# SCH_Orto-Idroponico_2021-09-24.net
KiCad netlist of a schematic drawn in EasyEDA
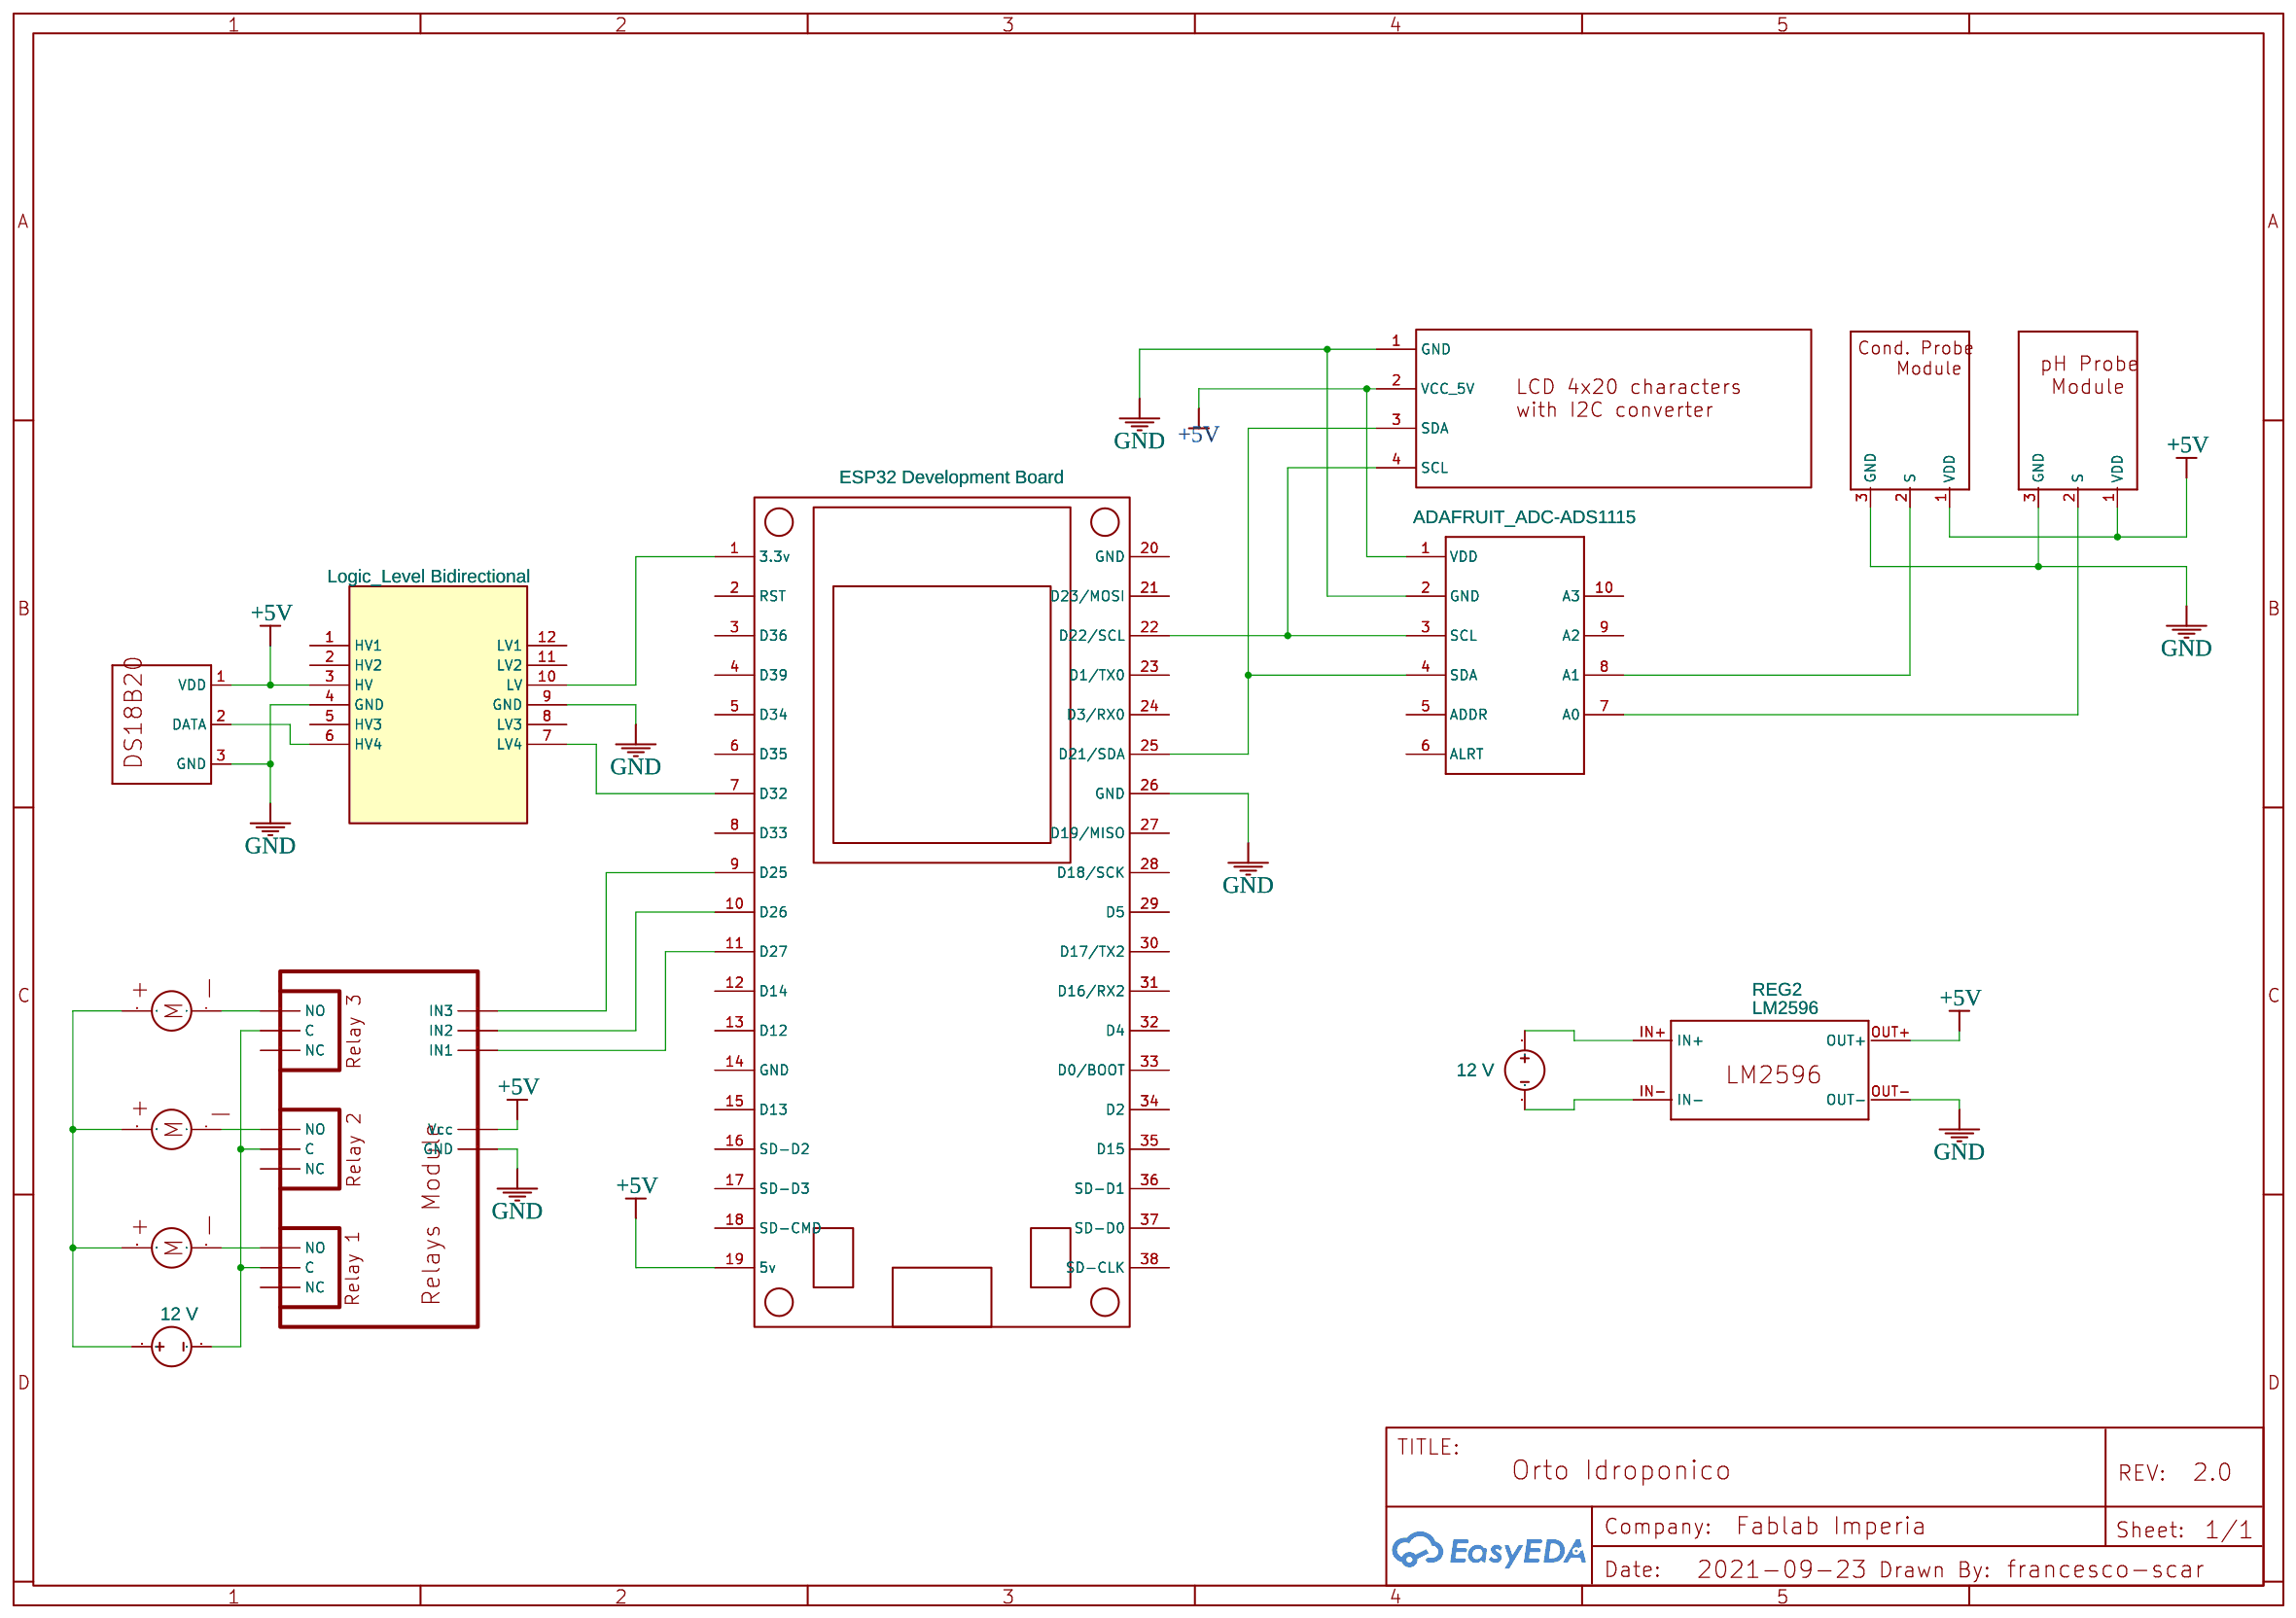
[diagram p0: schematic sheet]

(export (version "E")
  (design (tool "Eeschema 10.0.6"))
  (components
    (comp (ref "2") (value "ADAFRUIT_ADC-ADS1115") (libsource (lib "") (part "ADAFRUIT_ADC-ADS1115")))
    (comp (ref "P1")
      (value "Logic_Level Bidirectional")
      (libsource (lib "") (part "Logic_Level Bidirectional"))
    )
    (comp (ref "REG2") (value "LM2596") (libsource (lib "") (part "LM2596")))
    (comp (ref "T1") (value "DS18B20") (libsource (lib "") (part "DS18B20")))
    (comp (ref "T2") (value "pH probe module") (libsource (lib "") (part "pH probe module")))
    (comp (ref "T3")
      (value "conductivity probe module")
      (libsource (lib "") (part "conductivity probe module"))
    )
    (comp (ref "U1") (value "ESP32 Development Board") (libsource (lib "") (part "ESP32 Development Board")))
    (comp (ref "U2")
      (value "3_RELAYS_MODULE")
      (fields (field (name "BOM_Manufacturer Part") "3 Relays Module"))
      (libsource (lib "") (part "3_RELAYS_MODULE"))
    )
    (comp (ref "U3")
      (value "Nettigo LCD 4x20 I2C")
      (fields (field (name "BOM_Manufacturer Part") "2004A"))
      (libsource (lib "") (part "Nettigo LCD 4x20 I2C"))
    )
    (comp (ref "U4") (value "DC Motor") (libsource (lib "") (part "DC Motor")))
    (comp (ref "U5") (value "DC Motor") (libsource (lib "") (part "DC Motor_1")))
    (comp (ref "U6") (value "DC Motor") (libsource (lib "") (part "DC Motor")))
    (comp (ref "V1") (value "12 V") (libsource (lib "") (part "DC Power Source")))
    (comp (ref "V2") (value "12 V") (libsource (lib "") (part "DC Power Source_1")))
  )
  (nets
    (net (code "1") (name "+5V") (class "Default")
      (node (ref "2") (pin "1") (pinfunction "VDD_1") (pintype "bidirectional"))
      (node (ref "P1") (pin "3") (pinfunction "HV_3") (pintype "unspecified"))
      (node (ref "REG2") (pin "OUT+") (pinfunction "OUT+_OUT+") (pintype "bidirectional"))
      (node (ref "T1") (pin "1") (pinfunction "VDD_1") (pintype "passive"))
      (node (ref "T2") (pin "1") (pinfunction "VDD_1") (pintype "passive"))
      (node (ref "T3") (pin "1") (pinfunction "VDD_1") (pintype "passive"))
      (node (ref "U1") (pin "19") (pinfunction "5v_19") (pintype "passive"))
      (node (ref "U2") (pin "5") (pinfunction "Vcc_5") (pintype "unspecified"))
      (node (ref "U3") (pin "2") (pinfunction "VCC_5V_2") (pintype "unspecified"))
    )
    (net (code "2") (name "GND") (class "Default")
      (node (ref "2") (pin "2") (pinfunction "GND_2") (pintype "bidirectional"))
      (node (ref "P1") (pin "4") (pinfunction "GND_4") (pintype "unspecified"))
      (node (ref "P1") (pin "9") (pinfunction "GND_9") (pintype "unspecified"))
      (node (ref "REG2") (pin "OUT-") (pinfunction "OUT-_OUT-") (pintype "bidirectional"))
      (node (ref "T1") (pin "3") (pinfunction "GND_3") (pintype "passive"))
      (node (ref "T2") (pin "3") (pinfunction "GND_3") (pintype "passive"))
      (node (ref "T3") (pin "3") (pinfunction "GND_3") (pintype "passive"))
      (node (ref "U1") (pin "26") (pinfunction "GND_26") (pintype "passive"))
      (node (ref "U2") (pin "1") (pinfunction "GND_1") (pintype "unspecified"))
      (node (ref "U3") (pin "1") (pinfunction "GND_1") (pintype "unspecified"))
    )
    (net (code "3") (name "Net-(2-A0)") (class "Default")
      (node (ref "2") (pin "7") (pinfunction "A0_7") (pintype "bidirectional"))
      (node (ref "T2") (pin "2") (pinfunction "S_2") (pintype "unspecified"))
    )
    (net (code "4") (name "Net-(2-A1)") (class "Default")
      (node (ref "2") (pin "8") (pinfunction "A1_8") (pintype "bidirectional"))
      (node (ref "T3") (pin "2") (pinfunction "S_2") (pintype "unspecified"))
    )
    (net (code "5") (name "Net-(2-SCL)") (class "Default")
      (node (ref "2") (pin "3") (pinfunction "SCL_3") (pintype "bidirectional"))
      (node (ref "U1") (pin "22") (pinfunction "D22/SCL_22") (pintype "bidirectional"))
      (node (ref "U3") (pin "4") (pinfunction "SCL_4") (pintype "unspecified"))
    )
    (net (code "6") (name "Net-(2-SDA)") (class "Default")
      (node (ref "2") (pin "4") (pinfunction "SDA_4") (pintype "bidirectional"))
      (node (ref "U1") (pin "25") (pinfunction "D21/SDA_25") (pintype "bidirectional"))
      (node (ref "U3") (pin "3") (pinfunction "SDA_3") (pintype "unspecified"))
    )
    (net (code "7") (name "Net-(P1-HV4)") (class "Default")
      (node (ref "P1") (pin "6") (pinfunction "HV4_6") (pintype "unspecified"))
      (node (ref "T1") (pin "2") (pinfunction "DATA_2") (pintype "unspecified"))
    )
    (net (code "8") (name "Net-(P1-LV)") (class "Default")
      (node (ref "P1") (pin "10") (pinfunction "LV_10") (pintype "unspecified"))
      (node (ref "U1") (pin "1") (pinfunction "3.3v_1") (pintype "passive"))
    )
    (net (code "9") (name "Net-(P1-LV4)") (class "Default")
      (node (ref "P1") (pin "7") (pinfunction "LV4_7") (pintype "unspecified"))
      (node (ref "U1") (pin "7") (pinfunction "D32_7") (pintype "bidirectional"))
    )
    (net (code "10") (name "Net-(REG2-PadIN+)") (class "Default")
      (node (ref "REG2") (pin "IN+") (pinfunction "IN+_IN+") (pintype "bidirectional"))
      (node (ref "V1") (pin "1") (pinfunction "1_1") (pintype "unspecified"))
    )
    (net (code "11") (name "Net-(REG2-PadIN-)") (class "Default")
      (node (ref "REG2") (pin "IN-") (pinfunction "IN-_IN-") (pintype "bidirectional"))
      (node (ref "V1") (pin "2") (pinfunction "2_2") (pintype "unspecified"))
    )
    (net (code "12") (name "Net-(U1-D25)") (class "Default")
      (node (ref "U1") (pin "9") (pinfunction "D25_9") (pintype "bidirectional"))
      (node (ref "U2") (pin "4") (pinfunction "IN3_4") (pintype "unspecified"))
    )
    (net (code "13") (name "Net-(U1-D26)") (class "Default")
      (node (ref "U1") (pin "10") (pinfunction "D26_10") (pintype "bidirectional"))
      (node (ref "U2") (pin "3") (pinfunction "IN2_3") (pintype "unspecified"))
    )
    (net (code "14") (name "Net-(U1-D27)") (class "Default")
      (node (ref "U1") (pin "11") (pinfunction "D27_11") (pintype "bidirectional"))
      (node (ref "U2") (pin "2") (pinfunction "IN1_2") (pintype "unspecified"))
    )
    (net (code "15") (name "Net-(U2-C-Pad10)") (class "Default")
      (node (ref "U2") (pin "10") (pinfunction "C_10") (pintype "unspecified"))
      (node (ref "U2") (pin "13") (pinfunction "C_13") (pintype "unspecified"))
      (node (ref "U2") (pin "16") (pinfunction "C_16") (pintype "unspecified"))
      (node (ref "V2") (pin "2") (pinfunction "2_2") (pintype "unspecified"))
    )
    (net (code "16") (name "Net-(U2-NO-Pad11)") (class "Default")
      (node (ref "U2") (pin "11") (pinfunction "NO_11") (pintype "unspecified"))
      (node (ref "U6") (pin "1") (pinfunction "1_1") (pintype "unspecified"))
    )
    (net (code "17") (name "Net-(U2-NO-Pad14)") (class "Default")
      (node (ref "U2") (pin "14") (pinfunction "NO_14") (pintype "unspecified"))
      (node (ref "U5") (pin "1") (pinfunction "1_1") (pintype "unspecified"))
    )
    (net (code "18") (name "Net-(U2-NO-Pad17)") (class "Default")
      (node (ref "U2") (pin "17") (pinfunction "NO_17") (pintype "unspecified"))
      (node (ref "U4") (pin "1") (pinfunction "1_1") (pintype "unspecified"))
    )
    (net (code "19") (name "Net-(U4-Pad2)") (class "Default")
      (node (ref "U4") (pin "2") (pinfunction "2_2") (pintype "unspecified"))
      (node (ref "U5") (pin "2") (pinfunction "2_2") (pintype "unspecified"))
      (node (ref "U6") (pin "2") (pinfunction "2_2") (pintype "unspecified"))
      (node (ref "V2") (pin "1") (pinfunction "1_1") (pintype "unspecified"))
    )
    (net (code "20") (name "unconnected-(2-A2-Pad9)") (class "Default")
      (node (ref "2") (pin "9") (pinfunction "A2_9") (pintype "bidirectional"))
    )
    (net (code "21") (name "unconnected-(2-A3-Pad10)") (class "Default")
      (node (ref "2") (pin "10") (pinfunction "A3_10") (pintype "bidirectional"))
    )
    (net (code "22") (name "unconnected-(2-ADDR-Pad5)") (class "Default")
      (node (ref "2") (pin "5") (pinfunction "ADDR_5") (pintype "bidirectional"))
    )
    (net (code "23") (name "unconnected-(2-ALRT-Pad6)") (class "Default")
      (node (ref "2") (pin "6") (pinfunction "ALRT_6") (pintype "bidirectional"))
    )
    (net (code "24") (name "unconnected-(P1-HV1-Pad1)") (class "Default")
      (node (ref "P1") (pin "1") (pinfunction "HV1_1") (pintype "unspecified"))
    )
    (net (code "25") (name "unconnected-(P1-HV2-Pad2)") (class "Default")
      (node (ref "P1") (pin "2") (pinfunction "HV2_2") (pintype "unspecified"))
    )
    (net (code "26") (name "unconnected-(P1-HV3-Pad5)") (class "Default")
      (node (ref "P1") (pin "5") (pinfunction "HV3_5") (pintype "unspecified"))
    )
    (net (code "27") (name "unconnected-(P1-LV1-Pad12)") (class "Default")
      (node (ref "P1") (pin "12") (pinfunction "LV1_12") (pintype "unspecified"))
    )
    (net (code "28") (name "unconnected-(P1-LV2-Pad11)") (class "Default")
      (node (ref "P1") (pin "11") (pinfunction "LV2_11") (pintype "unspecified"))
    )
    (net (code "29") (name "unconnected-(P1-LV3-Pad8)") (class "Default")
      (node (ref "P1") (pin "8") (pinfunction "LV3_8") (pintype "unspecified"))
    )
    (net (code "30") (name "unconnected-(U1-D0{slash}BOOT-Pad33)") (class "Default")
      (node (ref "U1") (pin "33") (pinfunction "D0/BOOT_33") (pintype "bidirectional"))
    )
    (net (code "31") (name "unconnected-(U1-D1{slash}TX0-Pad23)") (class "Default")
      (node (ref "U1") (pin "23") (pinfunction "D1/TX0_23") (pintype "bidirectional"))
    )
    (net (code "32") (name "unconnected-(U1-D2-Pad34)") (class "Default")
      (node (ref "U1") (pin "34") (pinfunction "D2_34") (pintype "bidirectional"))
    )
    (net (code "33") (name "unconnected-(U1-D3{slash}RX0-Pad24)") (class "Default")
      (node (ref "U1") (pin "24") (pinfunction "D3/RX0_24") (pintype "bidirectional"))
    )
    (net (code "34") (name "unconnected-(U1-D4-Pad32)") (class "Default")
      (node (ref "U1") (pin "32") (pinfunction "D4_32") (pintype "bidirectional"))
    )
    (net (code "35") (name "unconnected-(U1-D5-Pad29)") (class "Default")
      (node (ref "U1") (pin "29") (pinfunction "D5_29") (pintype "bidirectional"))
    )
    (net (code "36") (name "unconnected-(U1-D12-Pad13)") (class "Default")
      (node (ref "U1") (pin "13") (pinfunction "D12_13") (pintype "bidirectional"))
    )
    (net (code "37") (name "unconnected-(U1-D13-Pad15)") (class "Default")
      (node (ref "U1") (pin "15") (pinfunction "D13_15") (pintype "bidirectional"))
    )
    (net (code "38") (name "unconnected-(U1-D14-Pad12)") (class "Default")
      (node (ref "U1") (pin "12") (pinfunction "D14_12") (pintype "bidirectional"))
    )
    (net (code "39") (name "unconnected-(U1-D15-Pad35)") (class "Default")
      (node (ref "U1") (pin "35") (pinfunction "D15_35") (pintype "bidirectional"))
    )
    (net (code "40") (name "unconnected-(U1-D16{slash}RX2-Pad31)") (class "Default")
      (node (ref "U1") (pin "31") (pinfunction "D16/RX2_31") (pintype "bidirectional"))
    )
    (net (code "41") (name "unconnected-(U1-D17{slash}TX2-Pad30)") (class "Default")
      (node (ref "U1") (pin "30") (pinfunction "D17/TX2_30") (pintype "bidirectional"))
    )
    (net (code "42") (name "unconnected-(U1-D18{slash}SCK-Pad28)") (class "Default")
      (node (ref "U1") (pin "28") (pinfunction "D18/SCK_28") (pintype "bidirectional"))
    )
    (net (code "43") (name "unconnected-(U1-D19{slash}MISO-Pad27)") (class "Default")
      (node (ref "U1") (pin "27") (pinfunction "D19/MISO_27") (pintype "bidirectional"))
    )
    (net (code "44") (name "unconnected-(U1-D23{slash}MOSI-Pad21)") (class "Default")
      (node (ref "U1") (pin "21") (pinfunction "D23/MOSI_21") (pintype "bidirectional"))
    )
    (net (code "45") (name "unconnected-(U1-D33-Pad8)") (class "Default")
      (node (ref "U1") (pin "8") (pinfunction "D33_8") (pintype "bidirectional"))
    )
    (net (code "46") (name "unconnected-(U1-D34-Pad5)") (class "Default")
      (node (ref "U1") (pin "5") (pinfunction "D34_5") (pintype "bidirectional"))
    )
    (net (code "47") (name "unconnected-(U1-D35-Pad6)") (class "Default")
      (node (ref "U1") (pin "6") (pinfunction "D35_6") (pintype "bidirectional"))
    )
    (net (code "48") (name "unconnected-(U1-D36-Pad3)") (class "Default")
      (node (ref "U1") (pin "3") (pinfunction "D36_3") (pintype "bidirectional"))
    )
    (net (code "49") (name "unconnected-(U1-D39-Pad4)") (class "Default")
      (node (ref "U1") (pin "4") (pinfunction "D39_4") (pintype "bidirectional"))
    )
    (net (code "50") (name "unconnected-(U1-GND-Pad14)") (class "Default")
      (node (ref "U1") (pin "14") (pinfunction "GND_14") (pintype "passive"))
    )
    (net (code "51") (name "unconnected-(U1-GND-Pad20)") (class "Default")
      (node (ref "U1") (pin "20") (pinfunction "GND_20") (pintype "passive"))
    )
    (net (code "52") (name "unconnected-(U1-RST-Pad2)") (class "Default")
      (node (ref "U1") (pin "2") (pinfunction "RST_2") (pintype "bidirectional"))
    )
    (net (code "53") (name "unconnected-(U1-SD-CLK-Pad38)") (class "Default")
      (node (ref "U1") (pin "38") (pinfunction "SD-CLK_38") (pintype "bidirectional"))
    )
    (net (code "54") (name "unconnected-(U1-SD-CMD-Pad18)") (class "Default")
      (node (ref "U1") (pin "18") (pinfunction "SD-CMD_18") (pintype "bidirectional"))
    )
    (net (code "55") (name "unconnected-(U1-SD-D0-Pad37)") (class "Default")
      (node (ref "U1") (pin "37") (pinfunction "SD-D0_37") (pintype "bidirectional"))
    )
    (net (code "56") (name "unconnected-(U1-SD-D1-Pad36)") (class "Default")
      (node (ref "U1") (pin "36") (pinfunction "SD-D1_36") (pintype "bidirectional"))
    )
    (net (code "57") (name "unconnected-(U1-SD-D2-Pad16)") (class "Default")
      (node (ref "U1") (pin "16") (pinfunction "SD-D2_16") (pintype "bidirectional"))
    )
    (net (code "58") (name "unconnected-(U1-SD-D3-Pad17)") (class "Default")
      (node (ref "U1") (pin "17") (pinfunction "SD-D3_17") (pintype "bidirectional"))
    )
    (net (code "59") (name "unconnected-(U2-NC-Pad9)") (class "Default")
      (node (ref "U2") (pin "9") (pinfunction "NC_9") (pintype "unspecified"))
    )
    (net (code "60") (name "unconnected-(U2-NC-Pad12)") (class "Default")
      (node (ref "U2") (pin "12") (pinfunction "NC_12") (pintype "unspecified"))
    )
    (net (code "61") (name "unconnected-(U2-NC-Pad15)") (class "Default")
      (node (ref "U2") (pin "15") (pinfunction "NC_15") (pintype "unspecified"))
    )
  )
)
